# REF-IN-BLE-NS_4-2.net
KiCad netlist of a schematic drawn in EAGLE
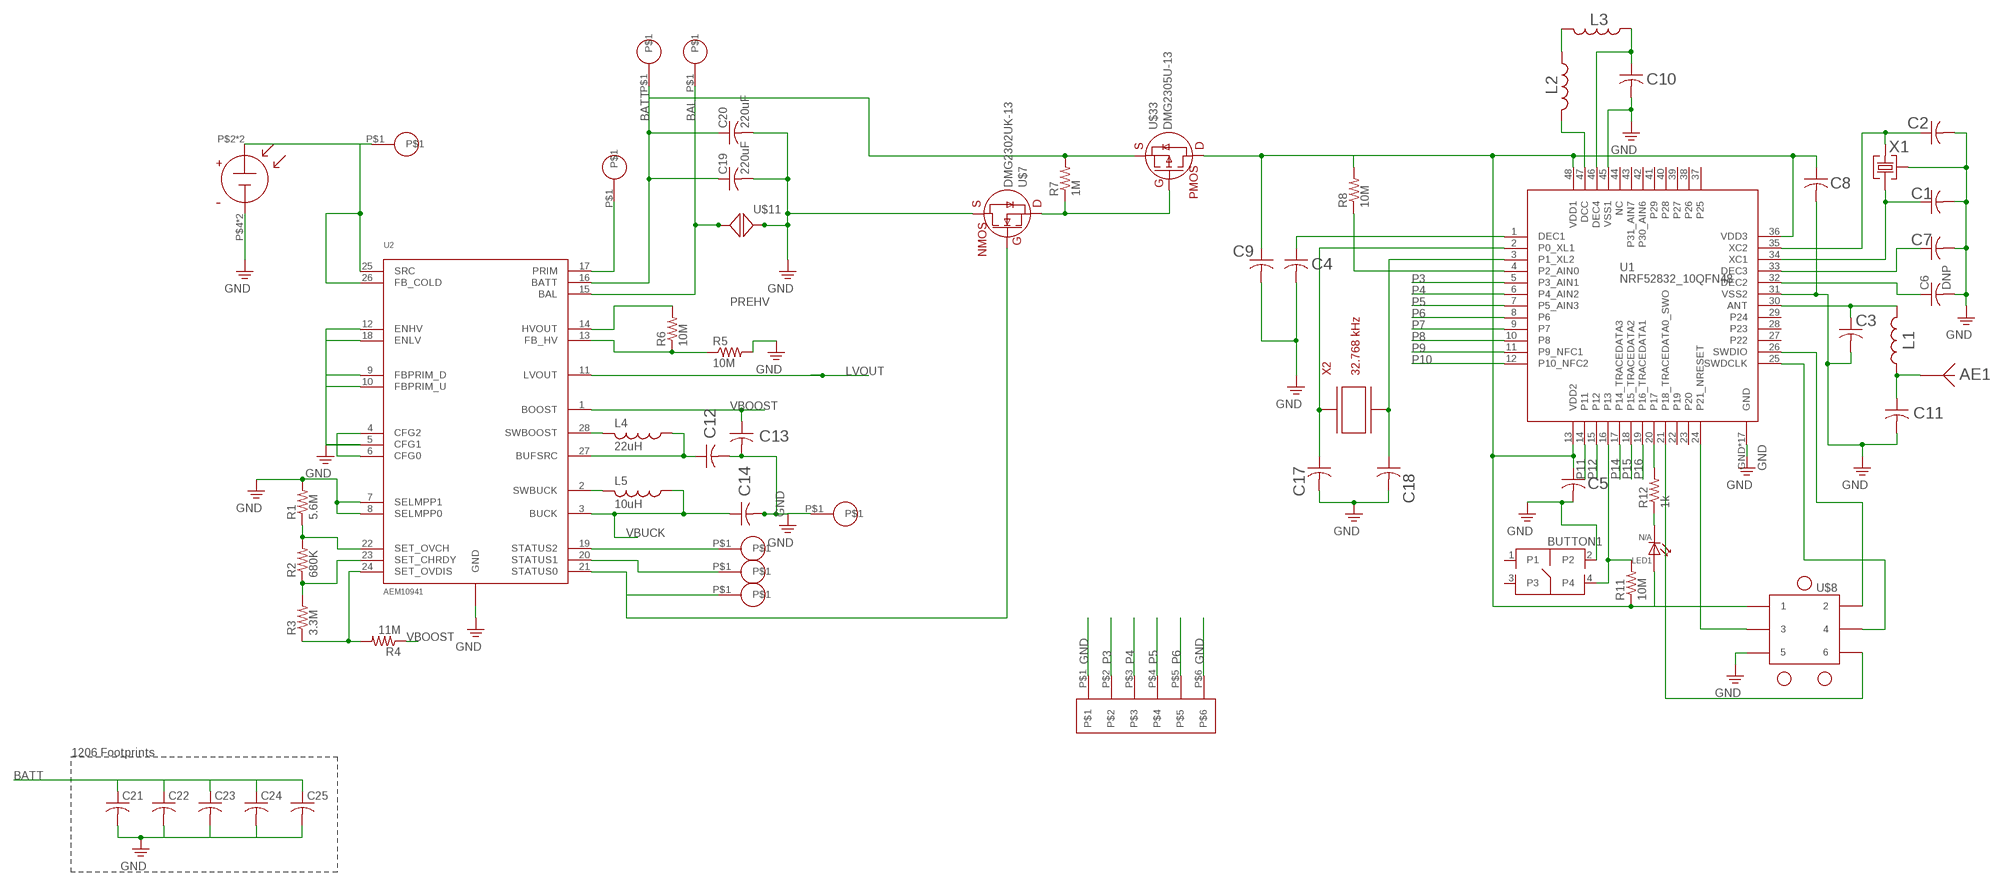
[diagram p0: schematic, sheet 1]

(export (version "E")
  (design (tool "Eeschema 10.0.6"))
  (components
    (comp (ref "AE1")
      (value "2.4GHZ_ANTENNAFLIPPED")
      (footprint "eagle-import:BLE_ANTENNA_NORDIC_FLIPPED")
      (libsource (lib "eagle-import") (part "2.4GHZ_ANTENNAFLIPPED"))
    )
    (comp (ref "BUTTON1")
      (value "MJTP1140")
      (footprint "eagle-import:MJTP1140A")
      (fields (field (name "MFG_PART#") "TL3315NF100Q "))
      (libsource (lib "eagle-import") (part "MJTP1140"))
    )
    (comp (ref "C1")
      (value "12pF")
      (footprint "eagle-import:C0603")
      (fields (field (name "MFG_PART#") "C0603C120J5GACTU"))
      (libsource (lib "eagle-import") (part "C-USC0603T-12PF"))
    )
    (comp (ref "C2")
      (value "12pF")
      (footprint "eagle-import:C0603")
      (fields (field (name "MFG_PART#") "C0603C120J5GACTU"))
      (libsource (lib "eagle-import") (part "C-USC0603T-12PF"))
    )
    (comp (ref "C3")
      (value "0.8pF")
      (footprint "eagle-import:C0603")
      (fields (field (name "MFG_PART#") "CBR06C808B5GAC "))
      (libsource (lib "eagle-import") (part "C-USC0603T-0.8PF"))
    )
    (comp (ref "C4")
      (value "100nF")
      (footprint "eagle-import:C0603")
      (fields (field (name "MFG_PART#") "CL10B104KB8NNNC"))
      (libsource (lib "eagle-import") (part "C-USC0603T-100NF"))
    )
    (comp (ref "C5")
      (value "100nF")
      (footprint "eagle-import:C0603")
      (fields (field (name "MFG_PART#") "CL10B104KB8NNNC"))
      (libsource (lib "eagle-import") (part "C-USC0603T-100NF"))
    )
    (comp (ref "C6")
      (value "DNP")
      (footprint "eagle-import:C0603")
      (libsource (lib "eagle-import") (part "C-USC0603"))
    )
    (comp (ref "C7")
      (value "100pF")
      (footprint "eagle-import:C0603")
      (fields (field (name "MFG_PART#") "CL10C101JB8NNNC"))
      (libsource (lib "eagle-import") (part "C-USC0603T-100PF"))
    )
    (comp (ref "C8")
      (value "100nF")
      (footprint "eagle-import:C0603")
      (fields (field (name "MFG_PART#") "CL10B104KB8NNNC"))
      (libsource (lib "eagle-import") (part "C-USC0603T-100NF"))
    )
    (comp (ref "C9")
      (value "4.7uF")
      (footprint "eagle-import:C0603")
      (fields (field (name "MFG_PART#") "CL10A475KQ8NNWC "))
      (libsource (lib "eagle-import") (part "C-USC0603T-4.7UF"))
    )
    (comp (ref "C10")
      (value "1uF")
      (footprint "eagle-import:C0603")
      (fields (field (name "MFG_PART#") "CL10A105KP8NNNC ") (field (name "PERCENTAGE") "10%"))
      (libsource (lib "eagle-import") (part "C-USC0603T-1UF"))
    )
    (comp (ref "C11")
      (value "DNP")
      (footprint "eagle-import:C0603")
      (libsource (lib "eagle-import") (part "C-USC0603"))
    )
    (comp (ref "C12")
      (value "10uF")
      (footprint "eagle-import:C0603")
      (fields (field (name "MFG_PART#") "GRM188R61E106MA73D"))
      (libsource (lib "eagle-import") (part "C-USC0603T-10UF"))
    )
    (comp (ref "C13")
      (value "22uF")
      (footprint "eagle-import:C0603")
      (fields (field (name "MFG_PART#") "GRM188R61A226ME15D"))
      (libsource (lib "eagle-import") (part "C-USC0603T-22UF"))
    )
    (comp (ref "C14")
      (value "10uF")
      (footprint "eagle-import:C0603")
      (fields (field (name "MFG_PART#") "GRM188R61E106MA73D"))
      (libsource (lib "eagle-import") (part "C-USC0603T-10UF"))
    )
    (comp (ref "C17")
      (value "12pF")
      (footprint "eagle-import:C0603")
      (fields (field (name "MFG_PART#") "C0603C120J5GACTU"))
      (libsource (lib "eagle-import") (part "C-USC0603T-12PF"))
    )
    (comp (ref "C18")
      (value "12pF")
      (footprint "eagle-import:C0603")
      (fields (field (name "MFG_PART#") "C0603C120J5GACTU"))
      (libsource (lib "eagle-import") (part "C-USC0603T-12PF"))
    )
    (comp (ref "C19")
      (value "220uF")
      (footprint "eagle-import:C1206")
      (fields (field (name "MFG_PART#") "GRM31CC80G227ME11L"))
      (libsource (lib "eagle-import") (part "C-USC1206T-220UF"))
    )
    (comp (ref "C20")
      (value "220uF")
      (footprint "eagle-import:C1206")
      (fields (field (name "MFG_PART#") "GRM31CC80G227ME11L"))
      (libsource (lib "eagle-import") (part "C-USC1206T-220UF"))
    )
    (comp (ref "C21")
      (value "C-USC1206")
      (footprint "eagle-import:C1206")
      (libsource (lib "eagle-import") (part "C-USC1206"))
    )
    (comp (ref "C22")
      (value "C-USC1206")
      (footprint "eagle-import:C1206")
      (libsource (lib "eagle-import") (part "C-USC1206"))
    )
    (comp (ref "C23")
      (value "C-USC1206")
      (footprint "eagle-import:C1206")
      (libsource (lib "eagle-import") (part "C-USC1206"))
    )
    (comp (ref "C24")
      (value "C-USC1206")
      (footprint "eagle-import:C1206")
      (libsource (lib "eagle-import") (part "C-USC1206"))
    )
    (comp (ref "C25")
      (value "C-USC1206")
      (footprint "eagle-import:C1206")
      (libsource (lib "eagle-import") (part "C-USC1206"))
    )
    (comp (ref "L1")
      (value "3.9nH")
      (footprint "eagle-import:L0603")
      (fields (field (name "MFG_PART#") "L-14C3N9SV4T "))
      (libsource (lib "eagle-import") (part "L0603V-3.9NH"))
    )
    (comp (ref "L2")
      (value "10uH")
      (footprint "eagle-import:L0603")
      (fields (field (name "MFG_PART#") "LBR2012T100M"))
      (libsource (lib "eagle-import") (part "L0603V-10UH"))
    )
    (comp (ref "L3")
      (value "15nH")
      (footprint "eagle-import:L0603")
      (fields (field (name "MFG_PART#") "L-14C15NJV4T"))
      (libsource (lib "eagle-import") (part "L0603V-15NH"))
    )
    (comp (ref "L4")
      (value "22uH")
      (footprint "eagle-import:L1206")
      (libsource (lib "eagle-import") (part "L1206"))
    )
    (comp (ref "L5")
      (value "10uH")
      (footprint "eagle-import:L0603")
      (fields (field (name "MFG_PART#") "LBR2012T100M"))
      (libsource (lib "eagle-import") (part "L0603V-10UH"))
    )
    (comp (ref "LED1")
      (value "N/A")
      (footprint "eagle-import:APT1608LZGCK")
      (fields (field (name "MFG_PART#") "APT1608LZGCK"))
      (libsource (lib "eagle-import") (part "APT1608LZGCK"))
    )
    (comp (ref "R1")
      (value "5.6M")
      (footprint "eagle-import:R0603")
      (libsource (lib "eagle-import") (part "R-US_R0603"))
    )
    (comp (ref "R2")
      (value "680K")
      (footprint "eagle-import:R0603")
      (libsource (lib "eagle-import") (part "R-US_R0603"))
    )
    (comp (ref "R3")
      (value "3.3M")
      (footprint "eagle-import:R0603")
      (libsource (lib "eagle-import") (part "R-US_R0603"))
    )
    (comp (ref "R4")
      (value "11M")
      (footprint "eagle-import:R0603")
      (libsource (lib "eagle-import") (part "R-US_R0603"))
    )
    (comp (ref "R5")
      (value "10M")
      (footprint "eagle-import:R0603")
      (libsource (lib "eagle-import") (part "R-US_R0603"))
    )
    (comp (ref "R6")
      (value "10M")
      (footprint "eagle-import:R0603")
      (libsource (lib "eagle-import") (part "R-US_R0603"))
    )
    (comp (ref "R7")
      (value "1M")
      (footprint "eagle-import:R0603")
      (libsource (lib "eagle-import") (part "R-US_R0603"))
    )
    (comp (ref "R8")
      (value "10M")
      (footprint "eagle-import:R0603")
      (libsource (lib "eagle-import") (part "R-US_R0603"))
    )
    (comp (ref "R11")
      (value "10M")
      (footprint "eagle-import:R0603")
      (libsource (lib "eagle-import") (part "R-US_R0603"))
    )
    (comp (ref "R12")
      (value "1k")
      (footprint "eagle-import:R0603")
      (libsource (lib "eagle-import") (part "R-US_R0603"))
    )
    (comp (ref "U$2")
      (value "BREAKOUT_PINS")
      (footprint "eagle-import:BREAKOUT_PINS")
      (libsource (lib "eagle-import") (part "BREAKOUT_PINS"))
    )
    (comp (ref "U$7")
      (value "DMG2302UK-13")
      (footprint "eagle-import:SOT-23-3-DIODESINC")
      (libsource (lib "eagle-import") (part "DMG2302UK-13"))
    )
    (comp (ref "U$8")
      (value "N/A")
      (footprint "eagle-import:TC2030-IDC")
      (libsource (lib "eagle-import") (part "TC2030-IDC"))
    )
    (comp (ref "U$11")
      (value "SOLDER_BRIGDECLOSED")
      (footprint "eagle-import:SOLDER_BRIDGE_CLOSED")
      (libsource (lib "eagle-import") (part "SOLDER_BRIGDECLOSED"))
    )
    (comp (ref "U$12")
      (value "N/A")
      (footprint "eagle-import:1MM_PAD")
      (libsource (lib "eagle-import") (part "1MM_PAD"))
    )
    (comp (ref "U$13")
      (value "N/A")
      (footprint "eagle-import:1MM_PAD")
      (libsource (lib "eagle-import") (part "1MM_PAD"))
    )
    (comp (ref "U$14")
      (value "N/A")
      (footprint "eagle-import:1MM_PAD")
      (libsource (lib "eagle-import") (part "1MM_PAD"))
    )
    (comp (ref "U$15")
      (value "N/A")
      (footprint "eagle-import:1MM_PAD")
      (libsource (lib "eagle-import") (part "1MM_PAD"))
    )
    (comp (ref "U$16")
      (value "SOLAR_CELL_LL200-2.4-37")
      (footprint "eagle-import:SOLAR_CELL_37X54MM")
      (libsource (lib "eagle-import") (part "SOLAR_CELL_LL200-2.4-37"))
    )
    (comp (ref "U$18")
      (value "N/A")
      (footprint "eagle-import:1MM_PAD")
      (libsource (lib "eagle-import") (part "1MM_PAD"))
    )
    (comp (ref "U$19")
      (value "N/A")
      (footprint "eagle-import:1MM_PAD")
      (libsource (lib "eagle-import") (part "1MM_PAD"))
    )
    (comp (ref "U$33")
      (value "DMG2305U-13")
      (footprint "eagle-import:SOT-23-3-DIODESINC")
      (libsource (lib "eagle-import") (part "DMG2305U-13"))
    )
    (comp (ref "U$35")
      (value "N/A")
      (footprint "eagle-import:1MM_PAD")
      (libsource (lib "eagle-import") (part "1MM_PAD"))
    )
    (comp (ref "U$36")
      (value "N/A")
      (footprint "eagle-import:1MM_PAD")
      (libsource (lib "eagle-import") (part "1MM_PAD"))
    )
    (comp (ref "U1")
      (value "NRF52832_10QFN48")
      (footprint "eagle-import:NRF52832_10")
      (fields (field (name "MFG_PART#") "NRF52832-QFAA-R"))
      (libsource (lib "eagle-import") (part "NRF52832_10QFN48"))
    )
    (comp (ref "U2")
      (value "AEM10941")
      (footprint "eagle-import:QFN28_5X5_05PITCH")
      (fields (field (name "MFG_PART#") "AEM10941-QFN "))
      (libsource (lib "eagle-import") (part "AEM10941"))
    )
    (comp (ref "X1")
      (value "32 MHz")
      (footprint "eagle-import:FA-128-EPSON")
      (fields (field (name "MFG_PART#") "FA-128 32.0000MF10Z-AJ3"))
      (libsource (lib "eagle-import") (part "FA-128-32MHZMF10Z-AJ5"))
    )
    (comp (ref "X2")
      (value "32.768 kHz")
      (footprint "eagle-import:FC-135")
      (fields (field (name "MFG_PART#") "FC-135 32.7680KA-AC"))
      (libsource (lib "eagle-import") (part "FC-135_32.7680KA-AC"))
    )
  )
  (nets
    (net (code "1") (name "/BAL") (class "Default")
      (node (ref "U$11") (pin "P$1") (pinfunction "P1_P$1") (pintype "bidirectional"))
      (node (ref "U$19") (pin "P$1") (pinfunction "P$1_P$1") (pintype "bidirectional"))
      (node (ref "U2") (pin "15") (pinfunction "BAL_15") (pintype "bidirectional"))
    )
    (net (code "2") (name "/BATT") (class "Default")
      (node (ref "C19") (pin "1") (pinfunction "1_1") (pintype "passive"))
      (node (ref "C20") (pin "1") (pinfunction "1_1") (pintype "passive"))
      (node (ref "C21") (pin "1") (pinfunction "1_1") (pintype "passive"))
      (node (ref "C22") (pin "1") (pinfunction "1_1") (pintype "passive"))
      (node (ref "C23") (pin "1") (pinfunction "1_1") (pintype "passive"))
      (node (ref "C24") (pin "1") (pinfunction "1_1") (pintype "passive"))
      (node (ref "C25") (pin "1") (pinfunction "1_1") (pintype "passive"))
      (node (ref "R7") (pin "2") (pinfunction "2_2") (pintype "passive"))
      (node (ref "U$18") (pin "P$1") (pinfunction "P$1_P$1") (pintype "bidirectional"))
      (node (ref "U$33") (pin "2") (pinfunction "S_2") (pintype "bidirectional"))
      (node (ref "U2") (pin "16") (pinfunction "BATT_16") (pintype "bidirectional"))
    )
    (net (code "3") (name "/LVOUT") (class "Default")
      (node (ref "U2") (pin "11") (pinfunction "LVOUT_11") (pintype "output"))
    )
    (net (code "4") (name "/P3") (class "Default")
      (node (ref "U$2") (pin "P$2") (pinfunction "P$2_P$2") (pintype "bidirectional"))
      (node (ref "U1") (pin "5") (pinfunction "P3_AIN1_5") (pintype "bidirectional"))
    )
    (net (code "5") (name "/P4") (class "Default")
      (node (ref "U$2") (pin "P$3") (pinfunction "P$3_P$3") (pintype "bidirectional"))
      (node (ref "U1") (pin "6") (pinfunction "P4_AIN2_6") (pintype "bidirectional"))
    )
    (net (code "6") (name "/P5") (class "Default")
      (node (ref "U$2") (pin "P$4") (pinfunction "P$4_P$4") (pintype "bidirectional"))
      (node (ref "U1") (pin "7") (pinfunction "P5_AIN3_7") (pintype "bidirectional"))
    )
    (net (code "7") (name "/P6") (class "Default")
      (node (ref "U$2") (pin "P$5") (pinfunction "P$5_P$5") (pintype "bidirectional"))
      (node (ref "U1") (pin "8") (pinfunction "P6_8") (pintype "bidirectional"))
    )
    (net (code "8") (name "/P7") (class "Default")
      (node (ref "U1") (pin "9") (pinfunction "P7_9") (pintype "bidirectional"))
    )
    (net (code "9") (name "/P8") (class "Default")
      (node (ref "U1") (pin "10") (pinfunction "P8_10") (pintype "bidirectional"))
    )
    (net (code "10") (name "/P9") (class "Default")
      (node (ref "U1") (pin "11") (pinfunction "P9_NFC1_11") (pintype "bidirectional"))
    )
    (net (code "11") (name "/P10") (class "Default")
      (node (ref "U1") (pin "12") (pinfunction "P10_NFC2_12") (pintype "bidirectional"))
    )
    (net (code "12") (name "/P11") (class "Default")
      (node (ref "U1") (pin "14") (pinfunction "P11_14") (pintype "bidirectional"))
    )
    (net (code "13") (name "/P12") (class "Default")
      (node (ref "U1") (pin "15") (pinfunction "P12_15") (pintype "bidirectional"))
    )
    (net (code "14") (name "/P14") (class "Default")
      (node (ref "U1") (pin "17") (pinfunction "P14_TRACEDATA3_17") (pintype "bidirectional"))
    )
    (net (code "15") (name "/P15") (class "Default")
      (node (ref "U1") (pin "18") (pinfunction "P15_TRACEDATA2_18") (pintype "bidirectional"))
    )
    (net (code "16") (name "/P16") (class "Default")
      (node (ref "U1") (pin "19") (pinfunction "P16_TRACEDATA1_19") (pintype "bidirectional"))
    )
    (net (code "17") (name "/PREHV") (class "Default")
      (node (ref "R6") (pin "2") (pinfunction "2_2") (pintype "passive"))
      (node (ref "U2") (pin "14") (pinfunction "HVOUT_14") (pintype "output"))
    )
    (net (code "18") (name "/VBOOST") (class "Default")
      (node (ref "C13") (pin "1") (pinfunction "1_1") (pintype "passive"))
      (node (ref "R4") (pin "1") (pinfunction "1_1") (pintype "passive"))
      (node (ref "U2") (pin "1") (pinfunction "BOOST_1") (pintype "bidirectional"))
    )
    (net (code "19") (name "/VBUCK") (class "Default")
      (node (ref "C14") (pin "1") (pinfunction "1_1") (pintype "passive"))
      (node (ref "L5") (pin "1") (pinfunction "1_1") (pintype "passive"))
      (node (ref "U2") (pin "3") (pinfunction "BUCK_3") (pintype "bidirectional"))
    )
    (net (code "20") (name "GND") (class "Default")
      (node (ref "BUTTON1") (pin "2") (pinfunction "P2_2") (pintype "bidirectional"))
      (node (ref "C1") (pin "2") (pinfunction "2_2") (pintype "passive"))
      (node (ref "C10") (pin "2") (pinfunction "2_2") (pintype "passive"))
      (node (ref "C11") (pin "2") (pinfunction "2_2") (pintype "passive"))
      (node (ref "C12") (pin "2") (pinfunction "2_2") (pintype "passive"))
      (node (ref "C13") (pin "2") (pinfunction "2_2") (pintype "passive"))
      (node (ref "C14") (pin "2") (pinfunction "2_2") (pintype "passive"))
      (node (ref "C17") (pin "2") (pinfunction "2_2") (pintype "passive"))
      (node (ref "C18") (pin "2") (pinfunction "2_2") (pintype "passive"))
      (node (ref "C19") (pin "2") (pinfunction "2_2") (pintype "passive"))
      (node (ref "C2") (pin "2") (pinfunction "2_2") (pintype "passive"))
      (node (ref "C20") (pin "2") (pinfunction "2_2") (pintype "passive"))
      (node (ref "C21") (pin "2") (pinfunction "2_2") (pintype "passive"))
      (node (ref "C22") (pin "2") (pinfunction "2_2") (pintype "passive"))
      (node (ref "C23") (pin "2") (pinfunction "2_2") (pintype "passive"))
      (node (ref "C24") (pin "2") (pinfunction "2_2") (pintype "passive"))
      (node (ref "C25") (pin "2") (pinfunction "2_2") (pintype "passive"))
      (node (ref "C3") (pin "2") (pinfunction "2_2") (pintype "passive"))
      (node (ref "C4") (pin "2") (pinfunction "2_2") (pintype "passive"))
      (node (ref "C5") (pin "2") (pinfunction "2_2") (pintype "passive"))
      (node (ref "C6") (pin "2") (pinfunction "2_2") (pintype "passive"))
      (node (ref "C7") (pin "2") (pinfunction "2_2") (pintype "passive"))
      (node (ref "C8") (pin "2") (pinfunction "2_2") (pintype "passive"))
      (node (ref "C9") (pin "2") (pinfunction "2_2") (pintype "passive"))
      (node (ref "R1") (pin "2") (pinfunction "2_2") (pintype "passive"))
      (node (ref "R5") (pin "2") (pinfunction "2_2") (pintype "passive"))
      (node (ref "U$11") (pin "P$2") (pinfunction "P2_P$2") (pintype "bidirectional"))
      (node (ref "U$16") (pin "P$4") (pinfunction "GND_P$4") (pintype "bidirectional"))
      (node (ref "U$16") (pin "P$5") (pinfunction "GND_P$5") (pintype "bidirectional"))
      (node (ref "U$2") (pin "P$1") (pinfunction "P$1_P$1") (pintype "bidirectional"))
      (node (ref "U$2") (pin "P$6") (pinfunction "P$6_P$6") (pintype "bidirectional"))
      (node (ref "U$35") (pin "P$1") (pinfunction "P$1_P$1") (pintype "bidirectional"))
      (node (ref "U$7") (pin "2") (pinfunction "S_2") (pintype "bidirectional"))
      (node (ref "U$8") (pin "P5") (pinfunction "5_P5") (pintype "bidirectional"))
      (node (ref "U1") (pin "31") (pinfunction "VSS2_31") (pintype "bidirectional"))
      (node (ref "U1") (pin "45") (pinfunction "VSS1_45") (pintype "bidirectional"))
      (node (ref "U1") (pin "GND") (pinfunction "GND_GND") (pintype "bidirectional"))
      (node (ref "U1") (pin "P$10") (pinfunction "GND_P$10") (pintype "bidirectional"))
      (node (ref "U1") (pin "P$11") (pinfunction "GND_P$11") (pintype "bidirectional"))
      (node (ref "U1") (pin "P$12") (pinfunction "GND_P$12") (pintype "bidirectional"))
      (node (ref "U1") (pin "P$13") (pinfunction "GND_P$13") (pintype "bidirectional"))
      (node (ref "U1") (pin "P$14") (pinfunction "GND_P$14") (pintype "bidirectional"))
      (node (ref "U1") (pin "P$15") (pinfunction "GND_P$15") (pintype "bidirectional"))
      (node (ref "U1") (pin "P$16") (pinfunction "GND_P$16") (pintype "bidirectional"))
      (node (ref "U1") (pin "P$17") (pinfunction "GND_P$17") (pintype "bidirectional"))
      (node (ref "U1") (pin "P$2") (pinfunction "GND_P$2") (pintype "bidirectional"))
      (node (ref "U1") (pin "P$3") (pinfunction "GND_P$3") (pintype "bidirectional"))
      (node (ref "U1") (pin "P$4") (pinfunction "GND_P$4") (pintype "bidirectional"))
      (node (ref "U1") (pin "P$5") (pinfunction "GND_P$5") (pintype "bidirectional"))
      (node (ref "U1") (pin "P$6") (pinfunction "GND_P$6") (pintype "bidirectional"))
      (node (ref "U1") (pin "P$7") (pinfunction "GND_P$7") (pintype "bidirectional"))
      (node (ref "U1") (pin "P$8") (pinfunction "GND_P$8") (pintype "bidirectional"))
      (node (ref "U1") (pin "P$9") (pinfunction "GND_P$9") (pintype "bidirectional"))
      (node (ref "U2") (pin "10") (pinfunction "FBPRIM_U_10") (pintype "bidirectional"))
      (node (ref "U2") (pin "12") (pinfunction "ENHV_12") (pintype "input"))
      (node (ref "U2") (pin "18") (pinfunction "ENLV_18") (pintype "input"))
      (node (ref "U2") (pin "4") (pinfunction "CFG2_4") (pintype "input"))
      (node (ref "U2") (pin "5") (pinfunction "CFG1_5") (pintype "input"))
      (node (ref "U2") (pin "6") (pinfunction "CFG0_6") (pintype "input"))
      (node (ref "U2") (pin "7") (pinfunction "SELMPP1_7") (pintype "input"))
      (node (ref "U2") (pin "8") (pinfunction "SELMPP0_8") (pintype "input"))
      (node (ref "U2") (pin "9") (pinfunction "FBPRIM_D_9") (pintype "bidirectional"))
      (node (ref "U2") (pin "GND") (pinfunction "GND_GND") (pintype "power_in"))
      (node (ref "U2") (pin "GND1") (pinfunction "GND_GND1") (pintype "power_in"))
      (node (ref "U2") (pin "GND2") (pinfunction "GND_GND2") (pintype "power_in"))
      (node (ref "U2") (pin "GND3") (pinfunction "GND_GND3") (pintype "power_in"))
      (node (ref "U2") (pin "GND4") (pinfunction "GND_GND4") (pintype "power_in"))
      (node (ref "U2") (pin "GND5") (pinfunction "GND_GND5") (pintype "power_in"))
      (node (ref "X1") (pin "P2") (pinfunction "P3_P2") (pintype "bidirectional"))
      (node (ref "X1") (pin "P4") (pinfunction "P3_P4") (pintype "bidirectional"))
    )
    (net (code "21") (name "Net-(AE1-PadP$1)") (class "Default")
      (node (ref "AE1") (pin "P$1") (pinfunction "P$1_P$1") (pintype "bidirectional"))
      (node (ref "C11") (pin "1") (pinfunction "1_1") (pintype "passive"))
      (node (ref "L1") (pin "1") (pinfunction "1_1") (pintype "passive"))
    )
    (net (code "22") (name "Net-(BUTTON1-P4)") (class "Default")
      (node (ref "BUTTON1") (pin "4") (pinfunction "P4_4") (pintype "bidirectional"))
      (node (ref "R11") (pin "2") (pinfunction "2_2") (pintype "passive"))
      (node (ref "U1") (pin "16") (pinfunction "P13_16") (pintype "bidirectional"))
    )
    (net (code "23") (name "Net-(L2-Pad1)") (class "Default")
      (node (ref "L2") (pin "1") (pinfunction "1_1") (pintype "passive"))
      (node (ref "L3") (pin "2") (pinfunction "2_2") (pintype "passive"))
    )
    (net (code "24") (name "Net-(L4-1)") (class "Default")
      (node (ref "C12") (pin "1") (pinfunction "1_1") (pintype "passive"))
      (node (ref "L4") (pin "P$1") (pinfunction "1_P$1") (pintype "passive"))
      (node (ref "U2") (pin "27") (pinfunction "BUFSRC_27") (pintype "bidirectional"))
    )
    (net (code "25") (name "Net-(L4-2)") (class "Default")
      (node (ref "L4") (pin "P$2") (pinfunction "2_P$2") (pintype "passive"))
      (node (ref "U2") (pin "28") (pinfunction "SWBOOST_28") (pintype "bidirectional"))
    )
    (net (code "26") (name "Net-(LED1-PadC)") (class "Default")
      (node (ref "LED1") (pin "C") (pinfunction "C_C") (pintype "bidirectional"))
      (node (ref "R12") (pin "1") (pinfunction "1_1") (pintype "passive"))
    )
    (net (code "27") (name "Net-(U$7-G)") (class "Default")
      (node (ref "U$15") (pin "P$1") (pinfunction "P$1_P$1") (pintype "bidirectional"))
      (node (ref "U$7") (pin "1") (pinfunction "G_1") (pintype "bidirectional"))
      (node (ref "U2") (pin "21") (pinfunction "STATUS0_21") (pintype "output"))
    )
    (net (code "28") (name "Net-(U$8-2)") (class "Default")
      (node (ref "U$8") (pin "P2") (pinfunction "2_P2") (pintype "bidirectional"))
      (node (ref "U1") (pin "26") (pinfunction "SWDIO_26") (pintype "bidirectional"))
    )
    (net (code "29") (name "Net-(U$8-3)") (class "Default")
      (node (ref "U$8") (pin "P3") (pinfunction "3_P3") (pintype "bidirectional"))
      (node (ref "U1") (pin "24") (pinfunction "P21_NRESET_24") (pintype "bidirectional"))
    )
    (net (code "30") (name "Net-(U$8-4)") (class "Default")
      (node (ref "U$8") (pin "P4") (pinfunction "4_P4") (pintype "bidirectional"))
      (node (ref "U1") (pin "25") (pinfunction "SWDCLK_25") (pintype "bidirectional"))
    )
    (net (code "31") (name "Net-(U$8-6)") (class "Default")
      (node (ref "U$8") (pin "P6") (pinfunction "6_P6") (pintype "bidirectional"))
      (node (ref "U1") (pin "21") (pinfunction "P18_TRACEDATA0_SWO_21") (pintype "bidirectional"))
    )
    (net (code "32") (name "Net-(U$33-D)") (class "Default")
      (node (ref "C5") (pin "1") (pinfunction "1_1") (pintype "passive"))
      (node (ref "C8") (pin "1") (pinfunction "1_1") (pintype "passive"))
      (node (ref "C9") (pin "1") (pinfunction "1_1") (pintype "passive"))
      (node (ref "LED1") (pin "A") (pinfunction "A_A") (pintype "bidirectional"))
      (node (ref "R11") (pin "1") (pinfunction "1_1") (pintype "passive"))
      (node (ref "R8") (pin "2") (pinfunction "2_2") (pintype "passive"))
      (node (ref "U$33") (pin "3") (pinfunction "D_3") (pintype "bidirectional"))
      (node (ref "U$8") (pin "P1") (pinfunction "1_P1") (pintype "bidirectional"))
      (node (ref "U1") (pin "13") (pinfunction "VDD2_13") (pintype "bidirectional"))
      (node (ref "U1") (pin "36") (pinfunction "VDD3_36") (pintype "bidirectional"))
      (node (ref "U1") (pin "48") (pinfunction "VDD1_48") (pintype "bidirectional"))
    )
    (net (code "33") (name "Net-(U$33-G)") (class "Default")
      (node (ref "R7") (pin "1") (pinfunction "1_1") (pintype "passive"))
      (node (ref "U$33") (pin "1") (pinfunction "G_1") (pintype "bidirectional"))
      (node (ref "U$7") (pin "3") (pinfunction "D_3") (pintype "bidirectional"))
    )
    (net (code "34") (name "Net-(U1-ANT)") (class "Default")
      (node (ref "C3") (pin "1") (pinfunction "1_1") (pintype "passive"))
      (node (ref "L1") (pin "2") (pinfunction "2_2") (pintype "passive"))
      (node (ref "U1") (pin "30") (pinfunction "ANT_30") (pintype "bidirectional"))
    )
    (net (code "35") (name "Net-(U1-DCC)") (class "Default")
      (node (ref "L2") (pin "2") (pinfunction "2_2") (pintype "passive"))
      (node (ref "U1") (pin "47") (pinfunction "DCC_47") (pintype "bidirectional"))
    )
    (net (code "36") (name "Net-(U1-DEC1)") (class "Default")
      (node (ref "C4") (pin "1") (pinfunction "1_1") (pintype "passive"))
      (node (ref "U1") (pin "1") (pinfunction "DEC1_1") (pintype "bidirectional"))
    )
    (net (code "37") (name "Net-(U1-DEC2)") (class "Default")
      (node (ref "C6") (pin "1") (pinfunction "1_1") (pintype "passive"))
      (node (ref "U1") (pin "32") (pinfunction "DEC2_32") (pintype "bidirectional"))
    )
    (net (code "38") (name "Net-(U1-DEC3)") (class "Default")
      (node (ref "C7") (pin "1") (pinfunction "1_1") (pintype "passive"))
      (node (ref "U1") (pin "33") (pinfunction "DEC3_33") (pintype "bidirectional"))
    )
    (net (code "39") (name "Net-(U1-DEC4)") (class "Default")
      (node (ref "C10") (pin "1") (pinfunction "1_1") (pintype "passive"))
      (node (ref "L3") (pin "1") (pinfunction "1_1") (pintype "passive"))
      (node (ref "U1") (pin "46") (pinfunction "DEC4_46") (pintype "bidirectional"))
    )
    (net (code "40") (name "Net-(U1-P0_XL1)") (class "Default")
      (node (ref "C17") (pin "1") (pinfunction "1_1") (pintype "passive"))
      (node (ref "U1") (pin "2") (pinfunction "P0_XL1_2") (pintype "bidirectional"))
      (node (ref "X2") (pin "P$1") (pinfunction "P$1_P$1") (pintype "bidirectional"))
    )
    (net (code "41") (name "Net-(U1-P1_XL2)") (class "Default")
      (node (ref "C18") (pin "1") (pinfunction "1_1") (pintype "passive"))
      (node (ref "U1") (pin "3") (pinfunction "P1_XL2_3") (pintype "bidirectional"))
      (node (ref "X2") (pin "P$2") (pinfunction "P$2_P$2") (pintype "bidirectional"))
    )
    (net (code "42") (name "Net-(U1-P2_AIN0)") (class "Default")
      (node (ref "R8") (pin "1") (pinfunction "1_1") (pintype "passive"))
      (node (ref "U1") (pin "4") (pinfunction "P2_AIN0_4") (pintype "bidirectional"))
    )
    (net (code "43") (name "Net-(U1-P17)") (class "Default")
      (node (ref "R12") (pin "2") (pinfunction "2_2") (pintype "passive"))
      (node (ref "U1") (pin "20") (pinfunction "P17_20") (pintype "bidirectional"))
    )
    (net (code "44") (name "Net-(U1-XC1)") (class "Default")
      (node (ref "C1") (pin "1") (pinfunction "1_1") (pintype "passive"))
      (node (ref "U1") (pin "34") (pinfunction "XC1_34") (pintype "bidirectional"))
      (node (ref "X1") (pin "P3") (pinfunction "1_P3") (pintype "passive"))
    )
    (net (code "45") (name "Net-(U1-XC2)") (class "Default")
      (node (ref "C2") (pin "1") (pinfunction "1_1") (pintype "passive"))
      (node (ref "U1") (pin "35") (pinfunction "XC2_35") (pintype "bidirectional"))
      (node (ref "X1") (pin "P1") (pinfunction "2_P1") (pintype "passive"))
    )
    (net (code "46") (name "Net-(U2-FB_COLD)") (class "Default")
      (node (ref "U$16") (pin "P$2") (pinfunction "VOUT_P$2") (pintype "bidirectional"))
      (node (ref "U$16") (pin "P$3") (pinfunction "VOUT_P$3") (pintype "bidirectional"))
      (node (ref "U$36") (pin "P$1") (pinfunction "P$1_P$1") (pintype "bidirectional"))
      (node (ref "U2") (pin "25") (pinfunction "SRC_25") (pintype "input"))
      (node (ref "U2") (pin "26") (pinfunction "FB_COLD_26") (pintype "bidirectional"))
    )
    (net (code "47") (name "Net-(U2-FB_HV)") (class "Default")
      (node (ref "R5") (pin "1") (pinfunction "1_1") (pintype "passive"))
      (node (ref "R6") (pin "1") (pinfunction "1_1") (pintype "passive"))
      (node (ref "U2") (pin "13") (pinfunction "FB_HV_13") (pintype "input"))
    )
    (net (code "48") (name "Net-(U2-PRIM)") (class "Default")
      (node (ref "U$12") (pin "P$1") (pinfunction "P$1_P$1") (pintype "bidirectional"))
      (node (ref "U2") (pin "17") (pinfunction "PRIM_17") (pintype "bidirectional"))
    )
    (net (code "49") (name "Net-(U2-SET_CHRDY)") (class "Default")
      (node (ref "R2") (pin "1") (pinfunction "1_1") (pintype "passive"))
      (node (ref "R3") (pin "2") (pinfunction "2_2") (pintype "passive"))
      (node (ref "U2") (pin "23") (pinfunction "SET_CHRDY_23") (pintype "bidirectional"))
    )
    (net (code "50") (name "Net-(U2-SET_OVCH)") (class "Default")
      (node (ref "R1") (pin "1") (pinfunction "1_1") (pintype "passive"))
      (node (ref "R2") (pin "2") (pinfunction "2_2") (pintype "passive"))
      (node (ref "U2") (pin "22") (pinfunction "SET_OVCH_22") (pintype "bidirectional"))
    )
    (net (code "51") (name "Net-(U2-SET_OVDIS)") (class "Default")
      (node (ref "R3") (pin "1") (pinfunction "1_1") (pintype "passive"))
      (node (ref "R4") (pin "2") (pinfunction "2_2") (pintype "passive"))
      (node (ref "U2") (pin "24") (pinfunction "SET_OVDIS_24") (pintype "bidirectional"))
    )
    (net (code "52") (name "Net-(U2-STATUS1)") (class "Default")
      (node (ref "U$14") (pin "P$1") (pinfunction "P$1_P$1") (pintype "bidirectional"))
      (node (ref "U2") (pin "20") (pinfunction "STATUS1_20") (pintype "output"))
    )
    (net (code "53") (name "Net-(U2-STATUS2)") (class "Default")
      (node (ref "U$13") (pin "P$1") (pinfunction "P$1_P$1") (pintype "bidirectional"))
      (node (ref "U2") (pin "19") (pinfunction "STATUS2_19") (pintype "output"))
    )
    (net (code "54") (name "Net-(U2-SWBUCK)") (class "Default")
      (node (ref "L5") (pin "2") (pinfunction "2_2") (pintype "passive"))
      (node (ref "U2") (pin "2") (pinfunction "SWBUCK_2") (pintype "bidirectional"))
    )
    (net (code "55") (name "unconnected-(BUTTON1-P1-Pad1)") (class "Default")
      (node (ref "BUTTON1") (pin "1") (pinfunction "P1_1") (pintype "bidirectional"))
    )
    (net (code "56") (name "unconnected-(BUTTON1-P3-Pad3)") (class "Default")
      (node (ref "BUTTON1") (pin "3") (pinfunction "P3_3") (pintype "bidirectional"))
    )
    (net (code "57") (name "unconnected-(U1-NC-Pad44)") (class "Default")
      (node (ref "U1") (pin "44") (pinfunction "NC_44") (pintype "bidirectional"))
    )
    (net (code "58") (name "unconnected-(U1-P19-Pad22)") (class "Default")
      (node (ref "U1") (pin "22") (pinfunction "P19_22") (pintype "bidirectional"))
    )
    (net (code "59") (name "unconnected-(U1-P20-Pad23)") (class "Default")
      (node (ref "U1") (pin "23") (pinfunction "P20_23") (pintype "bidirectional"))
    )
    (net (code "60") (name "unconnected-(U1-P22-Pad27)") (class "Default")
      (node (ref "U1") (pin "27") (pinfunction "P22_27") (pintype "bidirectional"))
    )
    (net (code "61") (name "unconnected-(U1-P23-Pad28)") (class "Default")
      (node (ref "U1") (pin "28") (pinfunction "P23_28") (pintype "bidirectional"))
    )
    (net (code "62") (name "unconnected-(U1-P24-Pad29)") (class "Default")
      (node (ref "U1") (pin "29") (pinfunction "P24_29") (pintype "bidirectional"))
    )
    (net (code "63") (name "unconnected-(U1-P25-Pad37)") (class "Default")
      (node (ref "U1") (pin "37") (pinfunction "P25_37") (pintype "bidirectional"))
    )
    (net (code "64") (name "unconnected-(U1-P26-Pad38)") (class "Default")
      (node (ref "U1") (pin "38") (pinfunction "P26_38") (pintype "bidirectional"))
    )
    (net (code "65") (name "unconnected-(U1-P27-Pad39)") (class "Default")
      (node (ref "U1") (pin "39") (pinfunction "P27_39") (pintype "bidirectional"))
    )
    (net (code "66") (name "unconnected-(U1-P28-Pad40)") (class "Default")
      (node (ref "U1") (pin "40") (pinfunction "P28_40") (pintype "bidirectional"))
    )
    (net (code "67") (name "unconnected-(U1-P29-Pad41)") (class "Default")
      (node (ref "U1") (pin "41") (pinfunction "P29_41") (pintype "bidirectional"))
    )
    (net (code "68") (name "unconnected-(U1-P30_AIN6-Pad42)") (class "Default")
      (node (ref "U1") (pin "42") (pinfunction "P30_AIN6_42") (pintype "bidirectional"))
    )
    (net (code "69") (name "unconnected-(U1-P31_AIN7-Pad43)") (class "Default")
      (node (ref "U1") (pin "43") (pinfunction "P31_AIN7_43") (pintype "bidirectional"))
    )
  )
)
